# ej_2.net
KiCad netlist of a schematic drawn in Altium Designer
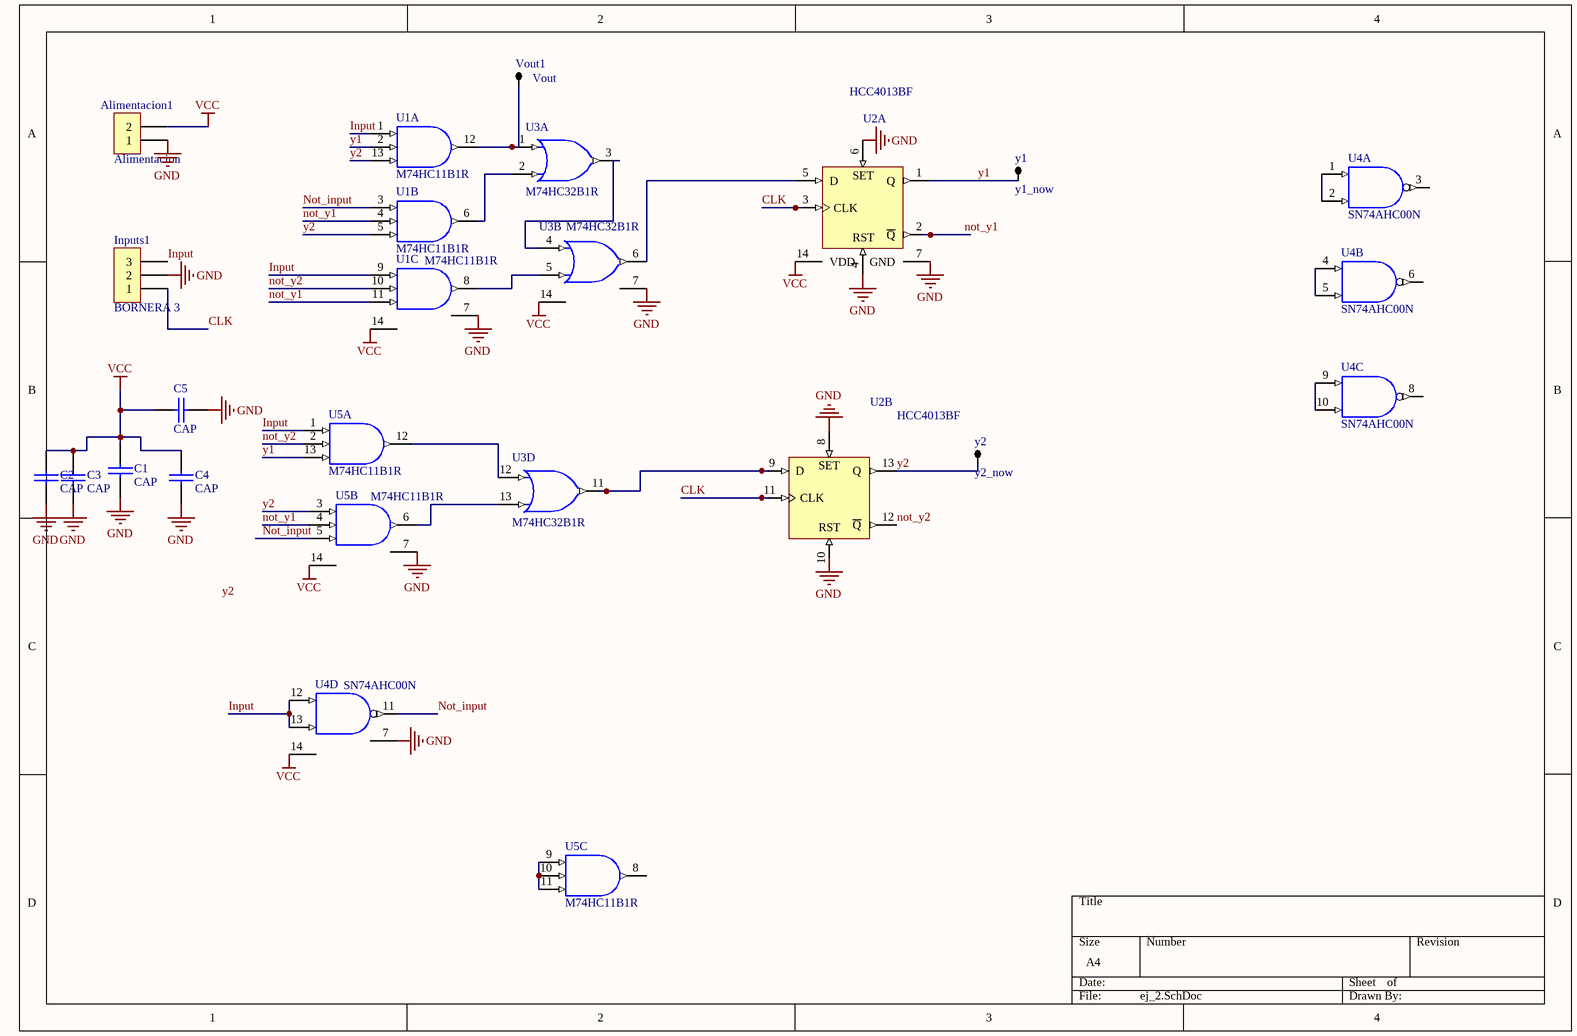
[diagram p0: ej_2.SchDoc]

(export (version "E")
  (design (tool "Eeschema 10.0.6"))
  (components
    (comp (ref "Alimentacion1")
      (value "Alimentacion")
      (footprint "BORNERA2")
      (libsource (lib "LIBEBAL") (part "BORNERA 2"))
    )
    (comp (ref "C1") (value "CAP") (footprint "CAP200") (libsource (lib "LIBEBAL") (part "CAP")))
    (comp (ref "C2") (value "CAP") (footprint "CAP200") (libsource (lib "LIBEBAL") (part "CAP")))
    (comp (ref "C3") (value "CAP") (footprint "CAP200") (libsource (lib "LIBEBAL") (part "CAP")))
    (comp (ref "C4") (value "CAP") (footprint "CAP200") (libsource (lib "LIBEBAL") (part "CAP")))
    (comp (ref "C5") (value "CAP") (footprint "CAP200") (libsource (lib "LIBEBAL") (part "CAP")))
    (comp (ref "Inputs1")
      (value "BORNERA 3")
      (footprint "BORNERA3")
      (libsource (lib "LIBEBAL") (part "BORNERA 3"))
    )
    (comp (ref "U1")
      (value "M74HC11B1R")
      (footprint "DIP14")
      (description "Triple 3-Input AND Gate")
      (fields (field (name "PUBLISHER") "Altium Limited"))
      (libsource (lib "ST Logic Gate") (part "M74HC11B1R"))
    )
    (comp (ref "U2")
      (value "HCC4013BF")
      (footprint "CDIP14")
      (description "Dual D-Type Flip-Flop")
      (fields (field (name "PUBLISHER") "Altium Limited"))
      (libsource (lib "ST Logic Flip-Flop") (part "HCC4013BF"))
    )
    (comp (ref "U3")
      (value "M74HC32B1R")
      (footprint "DIP14")
      (description "Quad 2-Input OR Gate")
      (fields (field (name "PUBLISHER") "Altium Limited"))
      (libsource (lib "ST Logic Gate") (part "M74HC32B1R"))
    )
    (comp (ref "U4")
      (value "SN74AHC00N")
      (footprint "N014")
      (description "Quadruple 2-Input Positive-NAND Gate")
      (fields (field (name "PUBLISHER") "Altium Limited"))
      (libsource (lib "TI Logic Gate 1") (part "SN74AHC00N"))
    )
    (comp (ref "U5")
      (value "M74HC11B1R")
      (footprint "DIP14")
      (description "Triple 3-Input AND Gate")
      (fields (field (name "PUBLISHER") "Altium Limited"))
      (libsource (lib "ST Logic Gate") (part "M74HC11B1R"))
    )
    (comp (ref "Vout1") (value "Vout") (footprint "TPTH") (libsource (lib "LIBEBAL") (part "TP")))
    (comp (ref "y1") (value "y1_now") (footprint "TPTH") (libsource (lib "LIBEBAL") (part "TP")))
    (comp (ref "y2") (value "y2_now") (footprint "TPTH") (libsource (lib "LIBEBAL") (part "TP")))
  )
  (nets
    (net (code "1") (name "/CLK") (class "Default")
      (node (ref "Inputs1") (pin "1") (pinfunction "1_1") (pintype "passive"))
      (node (ref "U2") (pin "11") (pinfunction "CLK_11") (pintype "input"))
      (node (ref "U2") (pin "3") (pinfunction "CLK_3") (pintype "input"))
    )
    (net (code "2") (name "/Input") (class "Default")
      (node (ref "Inputs1") (pin "3") (pinfunction "3_3") (pintype "passive"))
      (node (ref "U1") (pin "1") (pinfunction "A_1") (pintype "input"))
      (node (ref "U1") (pin "9") (pinfunction "A_9") (pintype "input"))
      (node (ref "U4") (pin "12") (pinfunction "A_12") (pintype "input"))
      (node (ref "U4") (pin "13") (pinfunction "B_13") (pintype "input"))
      (node (ref "U5") (pin "1") (pinfunction "A_1") (pintype "input"))
    )
    (net (code "3") (name "/Not_input") (class "Default")
      (node (ref "U1") (pin "3") (pinfunction "A_3") (pintype "input"))
      (node (ref "U4") (pin "11") (pinfunction "Y_11") (pintype "output"))
      (node (ref "U5") (pin "5") (pinfunction "C_5") (pintype "input"))
    )
    (net (code "4") (name "/not_y1") (class "Default")
      (node (ref "U1") (pin "11") (pinfunction "C_11") (pintype "input"))
      (node (ref "U1") (pin "4") (pinfunction "B_4") (pintype "input"))
      (node (ref "U2") (pin "2") (pinfunction "~{Q}_2") (pintype "output"))
      (node (ref "U5") (pin "4") (pinfunction "B_4") (pintype "input"))
    )
    (net (code "5") (name "/not_y2") (class "Default")
      (node (ref "U1") (pin "10") (pinfunction "B_10") (pintype "input"))
      (node (ref "U2") (pin "12") (pinfunction "~{Q}_12") (pintype "output"))
      (node (ref "U5") (pin "2") (pinfunction "B_2") (pintype "input"))
    )
    (net (code "6") (name "/y1") (class "Default")
      (node (ref "U1") (pin "2") (pinfunction "B_2") (pintype "input"))
      (node (ref "U2") (pin "1") (pinfunction "Q_1") (pintype "output"))
      (node (ref "U5") (pin "13") (pinfunction "C_13") (pintype "input"))
      (node (ref "y1") (pin "1") (pinfunction "1_1") (pintype "passive"))
    )
    (net (code "7") (name "/y2") (class "Default")
      (node (ref "U1") (pin "13") (pinfunction "C_13") (pintype "input"))
      (node (ref "U1") (pin "5") (pinfunction "C_5") (pintype "input"))
      (node (ref "U2") (pin "13") (pinfunction "Q_13") (pintype "output"))
      (node (ref "U5") (pin "3") (pinfunction "A_3") (pintype "input"))
      (node (ref "y2") (pin "1") (pinfunction "1_1") (pintype "passive"))
    )
    (net (code "8") (name "GND") (class "Default")
      (node (ref "Alimentacion1") (pin "1") (pinfunction "1_1") (pintype "passive"))
      (node (ref "C1") (pin "2") (pinfunction "2_2") (pintype "passive"))
      (node (ref "C2") (pin "2") (pinfunction "2_2") (pintype "passive"))
      (node (ref "C3") (pin "2") (pinfunction "2_2") (pintype "passive"))
      (node (ref "C4") (pin "2") (pinfunction "2_2") (pintype "passive"))
      (node (ref "C5") (pin "2") (pinfunction "2_2") (pintype "passive"))
      (node (ref "Inputs1") (pin "2") (pinfunction "2_2") (pintype "passive"))
      (node (ref "U1") (pin "7") (pinfunction "GND_7") (pintype "power_in"))
      (node (ref "U2") (pin "4") (pinfunction "RST_4") (pintype "input"))
      (node (ref "U2") (pin "6") (pinfunction "S_6") (pintype "input"))
      (node (ref "U2") (pin "7") (pinfunction "GND_7") (pintype "power_in"))
      (node (ref "U2") (pin "8") (pinfunction "S_8") (pintype "input"))
      (node (ref "U3") (pin "7") (pinfunction "GND_7") (pintype "power_in"))
      (node (ref "U4") (pin "7") (pinfunction "GND_7") (pintype "power_in"))
      (node (ref "U5") (pin "7") (pinfunction "GND_7") (pintype "power_in"))
    )
    (net (code "9") (name "Net-(U1A-Y)") (class "Default")
      (node (ref "U1") (pin "12") (pinfunction "Y_12") (pintype "output"))
      (node (ref "U3") (pin "1") (pinfunction "A_1") (pintype "input"))
      (node (ref "Vout1") (pin "1") (pinfunction "1_1") (pintype "passive"))
    )
    (net (code "10") (name "Net-(U1B-Y)") (class "Default")
      (node (ref "U1") (pin "6") (pinfunction "Y_6") (pintype "output"))
      (node (ref "U3") (pin "2") (pinfunction "B_2") (pintype "input"))
    )
    (net (code "11") (name "Net-(U1C-Y)") (class "Default")
      (node (ref "U1") (pin "8") (pinfunction "Y_8") (pintype "output"))
      (node (ref "U3") (pin "5") (pinfunction "B_5") (pintype "input"))
    )
    (net (code "12") (name "Net-(U2A-D)") (class "Default")
      (node (ref "U2") (pin "5") (pinfunction "D_5") (pintype "input"))
      (node (ref "U3") (pin "6") (pinfunction "Y_6") (pintype "output"))
    )
    (net (code "13") (name "Net-(U2B-D)") (class "Default")
      (node (ref "U2") (pin "9") (pinfunction "D_9") (pintype "input"))
      (node (ref "U3") (pin "11") (pinfunction "Y_11") (pintype "output"))
    )
    (net (code "14") (name "Net-(U3A-Y)") (class "Default")
      (node (ref "U3") (pin "3") (pinfunction "Y_3") (pintype "output"))
      (node (ref "U3") (pin "4") (pinfunction "A_4") (pintype "input"))
    )
    (net (code "15") (name "Net-(U3D-A)") (class "Default")
      (node (ref "U3") (pin "12") (pinfunction "A_12") (pintype "input"))
      (node (ref "U5") (pin "12") (pinfunction "Y_12") (pintype "output"))
    )
    (net (code "16") (name "Net-(U3D-B)") (class "Default")
      (node (ref "U3") (pin "13") (pinfunction "B_13") (pintype "input"))
      (node (ref "U5") (pin "6") (pinfunction "Y_6") (pintype "output"))
    )
    (net (code "17") (name "Net-(U4A-A)") (class "Default")
      (node (ref "U4") (pin "1") (pinfunction "A_1") (pintype "input"))
      (node (ref "U4") (pin "2") (pinfunction "B_2") (pintype "input"))
    )
    (net (code "18") (name "Net-(U4B-A)") (class "Default")
      (node (ref "U4") (pin "4") (pinfunction "A_4") (pintype "input"))
      (node (ref "U4") (pin "5") (pinfunction "B_5") (pintype "input"))
    )
    (net (code "19") (name "Net-(U4C-A)") (class "Default")
      (node (ref "U4") (pin "10") (pinfunction "B_10") (pintype "input"))
      (node (ref "U4") (pin "9") (pinfunction "A_9") (pintype "input"))
    )
    (net (code "20") (name "Net-(U5C-A)") (class "Default")
      (node (ref "U5") (pin "10") (pinfunction "B_10") (pintype "input"))
      (node (ref "U5") (pin "11") (pinfunction "C_11") (pintype "input"))
      (node (ref "U5") (pin "9") (pinfunction "A_9") (pintype "input"))
    )
    (net (code "21") (name "VCC") (class "Default")
      (node (ref "Alimentacion1") (pin "2") (pinfunction "2_2") (pintype "passive"))
      (node (ref "C1") (pin "1") (pinfunction "1_1") (pintype "passive"))
      (node (ref "C2") (pin "1") (pinfunction "1_1") (pintype "passive"))
      (node (ref "C3") (pin "1") (pinfunction "1_1") (pintype "passive"))
      (node (ref "C4") (pin "1") (pinfunction "1_1") (pintype "passive"))
      (node (ref "C5") (pin "1") (pinfunction "1_1") (pintype "passive"))
      (node (ref "U1") (pin "14") (pinfunction "VCC_14") (pintype "power_in"))
      (node (ref "U2") (pin "14") (pinfunction "VDD_14") (pintype "power_in"))
      (node (ref "U3") (pin "14") (pinfunction "VCC_14") (pintype "power_in"))
      (node (ref "U4") (pin "14") (pinfunction "VCC_14") (pintype "power_in"))
      (node (ref "U5") (pin "14") (pinfunction "VCC_14") (pintype "power_in"))
    )
    (net (code "22") (name "unconnected-(U2B-RST-Pad10)") (class "Default")
      (node (ref "U2") (pin "10") (pinfunction "RST_10") (pintype "input"))
    )
    (net (code "23") (name "unconnected-(U4A-Y-Pad3)") (class "Default")
      (node (ref "U4") (pin "3") (pinfunction "Y_3") (pintype "output"))
    )
    (net (code "24") (name "unconnected-(U4B-Y-Pad6)") (class "Default")
      (node (ref "U4") (pin "6") (pinfunction "Y_6") (pintype "output"))
    )
    (net (code "25") (name "unconnected-(U4C-Y-Pad8)") (class "Default")
      (node (ref "U4") (pin "8") (pinfunction "Y_8") (pintype "output"))
    )
    (net (code "26") (name "unconnected-(U5C-Y-Pad8)") (class "Default")
      (node (ref "U5") (pin "8") (pinfunction "Y_8") (pintype "output"))
    )
  )
)
